# Supply.net
KiCad netlist of a schematic drawn in Altium Designer
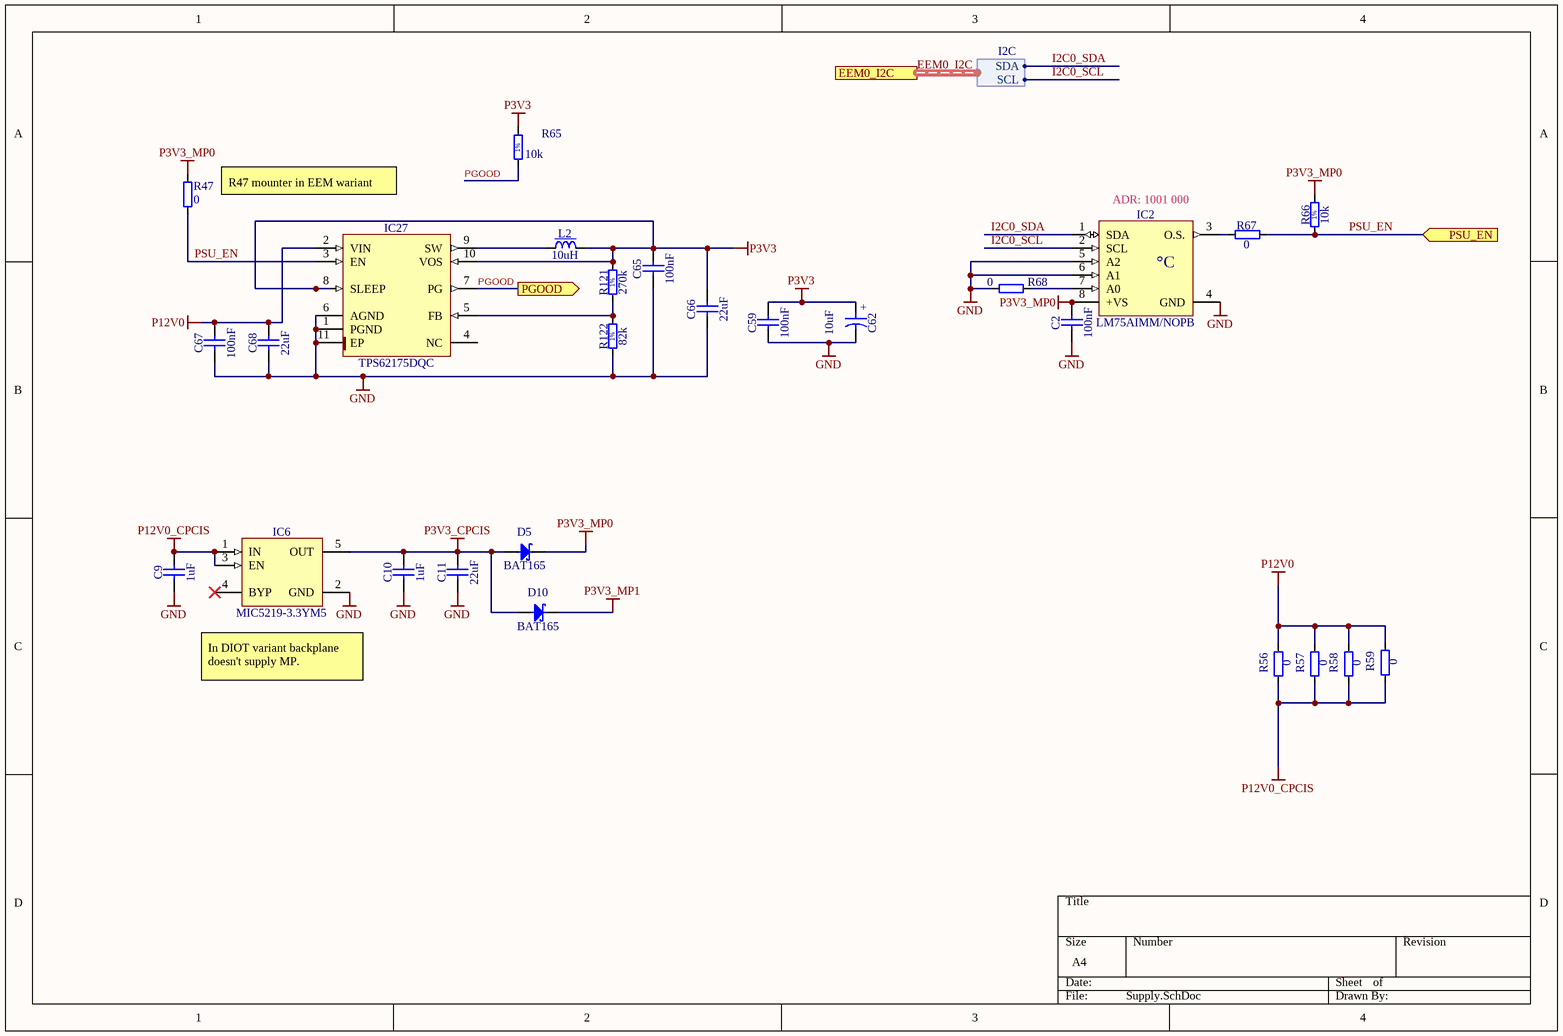
[diagram p0: Supply.SchDoc]

(export (version "E")
  (design (tool "Eeschema 10.0.6"))
  (components
    (comp (ref "C2")
      (value "100nF")
      (footprint "CAPC1005X55N")
      (description "Non-polarised capacitor")
      (fields
        (field (name "PART NUMBER") "CC0402_100NF_16V_10%_X5R")
        (field (name "VOLTAGE") "16V")
        (field (name "AUTHOR") "CERN DEM JLC")
      )
      (libsource (lib "Capacitors") (part "Capacitor - non polarized"))
    )
    (comp (ref "C9")
      (value "1uF")
      (footprint "CAPC1608X87N")
      (description "Non-polarised capacitor")
      (fields
        (field (name "PART NUMBER") "CC0603_1UF_25V_10%_X7R")
        (field (name "VOLTAGE") "25V")
        (field (name "AUTHOR") "CERN DEM JLC")
      )
      (libsource (lib "Capacitors") (part "Capacitor - non polarized"))
    )
    (comp (ref "C10")
      (value "1uF")
      (footprint "CAPC1608X87N")
      (description "Non-polarised capacitor")
      (fields
        (field (name "PART NUMBER") "CC0603_1UF_25V_10%_X7R")
        (field (name "VOLTAGE") "25V")
        (field (name "AUTHOR") "CERN DEM JLC")
      )
      (libsource (lib "Capacitors") (part "Capacitor - non polarized"))
    )
    (comp (ref "C11")
      (value "22uF")
      (footprint "CAPC1608X90N")
      (description "Non-polarised capacitor")
      (fields
        (field (name "PART NUMBER") "CC0603_22UF_6.3V_20%_X5R")
        (field (name "VOLTAGE") "6.3V")
        (field (name "AUTHOR") "CERN DEM JLC")
      )
      (libsource (lib "Capacitors") (part "Capacitor - non polarized"))
    )
    (comp (ref "C59")
      (value "100nF")
      (footprint "CAPC1005X55N")
      (description "Non-polarised capacitor")
      (fields
        (field (name "PART NUMBER") "CC0402_100NF_16V_10%_X5R")
        (field (name "VOLTAGE") "16V")
        (field (name "AUTHOR") "CERN DEM JLC")
      )
      (libsource (lib "Capacitors") (part "Capacitor - non polarized"))
    )
    (comp (ref "C62")
      (value "10uF")
      (footprint "CAPAE430X540N")
      (description "Polarised capacitor")
      (fields
        (field (name "PART NUMBER") "CAE430-540_10UF_16V_20%")
        (field (name "VOLTAGE") "16V")
        (field (name "AUTHOR") "CERN DEM JLC")
      )
      (libsource (lib "Capacitors") (part "Capacitor - polarized"))
    )
    (comp (ref "C65")
      (value "100nF")
      (footprint "CAPC1005X55N")
      (description "Non-polarised capacitor")
      (fields
        (field (name "PART NUMBER") "CC0402_100NF_16V_10%_X5R")
        (field (name "VOLTAGE") "16V")
        (field (name "AUTHOR") "CERN DEM JLC")
      )
      (libsource (lib "Capacitors") (part "Capacitor - non polarized"))
    )
    (comp (ref "C66")
      (value "22uF")
      (footprint "CAPC2012X135N")
      (description "Non-polarised capacitor")
      (fields
        (field (name "PART NUMBER") "CC0805_22UF_16V_10%_X5R")
        (field (name "VOLTAGE") "16V")
        (field (name "AUTHOR") "CERN DEM JLC")
      )
      (libsource (lib "Capacitors") (part "Capacitor - non polarized"))
    )
    (comp (ref "C67")
      (value "100nF")
      (footprint "CAPC1005X55N")
      (description "Non-polarised capacitor")
      (fields
        (field (name "PART NUMBER") "CC0402_100NF_16V_10%_X5R")
        (field (name "VOLTAGE") "16V")
        (field (name "AUTHOR") "CERN DEM JLC")
      )
      (libsource (lib "Capacitors") (part "Capacitor - non polarized"))
    )
    (comp (ref "C68")
      (value "22uF")
      (footprint "CAPC2012X135N")
      (description "Non-polarised capacitor")
      (fields
        (field (name "PART NUMBER") "CC0805_22UF_16V_10%_X5R")
        (field (name "VOLTAGE") "16V")
        (field (name "AUTHOR") "CERN DEM JLC")
      )
      (libsource (lib "Capacitors") (part "Capacitor - non polarized"))
    )
    (comp (ref "D5")
      (value "BAT165")
      (footprint "SOD2512X110N")
      (description "Schottky Diode")
      (fields
        (field (name "MANUFACTURER") "INFINEON")
        (field (name "VOLTAGE") "40V")
        (field (name "AUTHOR") "CERN DEM JLC")
      )
      (libsource (lib "ICs And Semiconductors") (part "Diode Schottky"))
    )
    (comp (ref "D10")
      (value "BAT165")
      (footprint "SOD2512X110N")
      (description "Schottky Diode")
      (fields
        (field (name "MANUFACTURER") "INFINEON")
        (field (name "VOLTAGE") "40V")
        (field (name "AUTHOR") "CERN DEM JLC")
      )
      (libsource (lib "ICs And Semiconductors") (part "Diode Schottky"))
    )
    (comp (ref "IC2")
      (value "LM75AIMM/NOPB")
      (footprint "SOP65P490X109-8N")
      (description "Digital Temperature Sensor and Thermal Watchdog with Two-Wire Interface")
      (fields (field (name "MANUFACTURER") "TEXAS INSTRUMENTS") (field (name "AUTHOR") "CERN DEM JLC"))
      (libsource (lib "ICs And Semiconductors") (part "LM75"))
    )
    (comp (ref "IC6")
      (value "MIC5219-3.3YM5")
      (footprint "SOT95P280X145-5N")
      (description "500mA Peak Output LDO Regulator")
      (fields (field (name "MANUFACTURER") "MICROCHIP TECHNOLOGY") (field (name "AUTHOR") "CERN DEM WB"))
      (libsource (lib "ICs And Semiconductors") (part "MIC5219-X.XYM5"))
    )
    (comp (ref "IC27")
      (value "TPS62175DQC")
      (footprint "SON50P200X300X80-11N-R94X250")
      (description "4.75-28VDC to 1-6VDC, 500mA Step-Down Converter With Sleep Mode")
      (fields (field (name "MANUFACTURER") "TEXAS INSTRUMENTS") (field (name "AUTHOR") "CERN DEM JMW"))
      (libsource (lib "ICs And Semiconductors") (part "TPS62175"))
    )
    (comp (ref "L2")
      (value "10uH")
      (footprint "IND_MURATA-PS_8400")
      (description "Inductor With Core")
      (fields
        (field (name "PART NUMBER") "IND_10UH_10%_MURATA-PS_8400")
        (field (name "POWER") "950mA")
        (field (name "AUTHOR") "CERN DEM JLC")
      )
      (libsource (lib "Inductors & Transformers") (part "Inductor With Magnetic core"))
    )
    (comp (ref "R47")
      (value "0")
      (footprint "RESC1005X40N")
      (description "Resistor")
      (fields
        (field (name "PART NUMBER") "R0402_0R_JUMPER")
        (field (name "MANUFACTURER") "GENERIC")
        (field (name "AUTHOR") "CERN DEM JLC")
      )
      (libsource (lib "Resistors") (part "Resistor"))
    )
    (comp (ref "R56")
      (value "0")
      (footprint "RESC1005X35N")
      (description "Resistor")
      (fields
        (field (name "PART NUMBER") "R0603_0R_JUMPER")
        (field (name "MANUFACTURER") "GENERIC")
        (field (name "AUTHOR") "CERN DEM JLC")
      )
      (libsource (lib "Resistors") (part "Resistor"))
    )
    (comp (ref "R57")
      (value "0")
      (footprint "RESC1005X35N")
      (description "Resistor")
      (fields
        (field (name "PART NUMBER") "R0603_0R_JUMPER")
        (field (name "MANUFACTURER") "GENERIC")
        (field (name "AUTHOR") "CERN DEM JLC")
      )
      (libsource (lib "Resistors") (part "Resistor"))
    )
    (comp (ref "R58")
      (value "0")
      (footprint "RESC1005X35N")
      (description "Resistor")
      (fields
        (field (name "PART NUMBER") "R0603_0R_JUMPER")
        (field (name "MANUFACTURER") "GENERIC")
        (field (name "AUTHOR") "CERN DEM JLC")
      )
      (libsource (lib "Resistors") (part "Resistor"))
    )
    (comp (ref "R59")
      (value "0")
      (footprint "RESC1005X35N")
      (description "Resistor")
      (fields
        (field (name "PART NUMBER") "R0603_0R_JUMPER")
        (field (name "MANUFACTURER") "GENERIC")
        (field (name "AUTHOR") "CERN DEM JLC")
      )
      (libsource (lib "Resistors") (part "Resistor"))
    )
    (comp (ref "R65")
      (value "10k")
      (footprint "RESC1005X40N")
      (description "Resistor - 1%")
      (fields
        (field (name "PART NUMBER") "R0402_10K_1%_0.0625W_100PPM")
        (field (name "POWER") "0.0625W")
        (field (name "AUTHOR") "CERN DEM JLC")
      )
      (libsource (lib "Resistors") (part "Resistor - 1%"))
    )
    (comp (ref "R66")
      (value "10k")
      (footprint "RESC1005X40N")
      (description "Resistor - 1%")
      (fields
        (field (name "PART NUMBER") "R0402_10K_1%_0.0625W_100PPM")
        (field (name "POWER") "0.0625W")
        (field (name "AUTHOR") "CERN DEM JLC")
      )
      (libsource (lib "Resistors") (part "Resistor - 1%"))
    )
    (comp (ref "R67")
      (value "0")
      (footprint "RESC1005X35N")
      (description "Resistor")
      (fields
        (field (name "PART NUMBER") "R0402_0R_JUMPER")
        (field (name "MANUFACTURER") "GENERIC")
        (field (name "AUTHOR") "CERN DEM JLC")
      )
      (libsource (lib "Resistors") (part "Resistor"))
    )
    (comp (ref "R68")
      (value "0")
      (footprint "RESC1005X35N")
      (description "Resistor")
      (fields
        (field (name "PART NUMBER") "R0402_0R_JUMPER")
        (field (name "MANUFACTURER") "GENERIC")
        (field (name "AUTHOR") "CERN DEM JLC")
      )
      (libsource (lib "Resistors") (part "Resistor"))
    )
    (comp (ref "R121")
      (value "270k")
      (footprint "RESC1608X55N")
      (description "Resistor - 1%")
      (fields
        (field (name "PART NUMBER") "R0603_270K_1%_0.1W_100PPM")
        (field (name "POWER") "0.1W")
        (field (name "AUTHOR") "CERN DEM JLC")
      )
      (libsource (lib "Resistors") (part "Resistor - 1%"))
    )
    (comp (ref "R122")
      (value "82k")
      (footprint "RESC1608X55N")
      (description "Resistor - 1%")
      (fields
        (field (name "PART NUMBER") "R0603_82K_1%_0.1W_100PPM")
        (field (name "POWER") "0.1W")
        (field (name "AUTHOR") "CERN DEM JLC")
      )
      (libsource (lib "Resistors") (part "Resistor - 1%"))
    )
  )
  (nets
    (net (code "3") (name "/I2C0_SCL") (class "Default")
      (node (ref "IC2") (pin "2") (pinfunction "SCL_2") (pintype "input"))
    )
    (net (code "4") (name "/I2C0_SDA") (class "Default")
      (node (ref "IC2") (pin "1") (pinfunction "SDA_1") (pintype "bidirectional"))
    )
    (net (code "5") (name "/PGOOD") (class "Default")
      (node (ref "IC27") (pin "7") (pinfunction "PG_7") (pintype "output"))
      (node (ref "R65") (pin "1") (pinfunction "1_1") (pintype "passive"))
    )
    (net (code "6") (name "/PSU_EN") (class "Default")
      (node (ref "IC27") (pin "3") (pinfunction "EN_3") (pintype "input"))
      (node (ref "R47") (pin "1") (pinfunction "1_1") (pintype "passive"))
      (node (ref "R66") (pin "1") (pinfunction "1_1") (pintype "passive"))
      (node (ref "R67") (pin "2") (pinfunction "2_2") (pintype "passive"))
    )
    (net (code "7") (name "GND") (class "Default")
      (node (ref "C10") (pin "1") (pinfunction "1_1") (pintype "passive"))
      (node (ref "C11") (pin "1") (pinfunction "1_1") (pintype "passive"))
      (node (ref "C2") (pin "1") (pinfunction "1_1") (pintype "passive"))
      (node (ref "C59") (pin "1") (pinfunction "1_1") (pintype "passive"))
      (node (ref "C62") (pin "2") (pinfunction "2_2") (pintype "passive"))
      (node (ref "C65") (pin "1") (pinfunction "1_1") (pintype "passive"))
      (node (ref "C66") (pin "1") (pinfunction "1_1") (pintype "passive"))
      (node (ref "C67") (pin "1") (pinfunction "1_1") (pintype "passive"))
      (node (ref "C68") (pin "1") (pinfunction "1_1") (pintype "passive"))
      (node (ref "C9") (pin "1") (pinfunction "1_1") (pintype "passive"))
      (node (ref "IC2") (pin "4") (pinfunction "GND_4") (pintype "power_in"))
      (node (ref "IC2") (pin "5") (pinfunction "A2_5") (pintype "input"))
      (node (ref "IC2") (pin "6") (pinfunction "A1_6") (pintype "input"))
      (node (ref "IC27") (pin "1") (pinfunction "PGND_1") (pintype "power_in"))
      (node (ref "IC27") (pin "11") (pinfunction "EP_11") (pintype "power_in"))
      (node (ref "IC27") (pin "6") (pinfunction "AGND_6") (pintype "power_in"))
      (node (ref "IC6") (pin "2") (pinfunction "GND_2") (pintype "power_in"))
      (node (ref "R122") (pin "1") (pinfunction "1_1") (pintype "passive"))
      (node (ref "R68") (pin "1") (pinfunction "1_1") (pintype "passive"))
    )
    (net (code "8") (name "Net-(IC2-A0)") (class "Default")
      (node (ref "IC2") (pin "7") (pinfunction "A0_7") (pintype "input"))
      (node (ref "R68") (pin "2") (pinfunction "2_2") (pintype "passive"))
    )
    (net (code "9") (name "Net-(IC2-O.S.)") (class "Default")
      (node (ref "IC2") (pin "3") (pinfunction "O.S._3") (pintype "output"))
      (node (ref "R67") (pin "1") (pinfunction "1_1") (pintype "passive"))
    )
    (net (code "10") (name "Net-(IC27-FB)") (class "Default")
      (node (ref "IC27") (pin "5") (pinfunction "FB_5") (pintype "input"))
      (node (ref "R121") (pin "1") (pinfunction "1_1") (pintype "passive"))
      (node (ref "R122") (pin "2") (pinfunction "2_2") (pintype "passive"))
    )
    (net (code "11") (name "Net-(IC27-SW)") (class "Default")
      (node (ref "IC27") (pin "9") (pinfunction "SW_9") (pintype "output"))
      (node (ref "L2") (pin "1") (pinfunction "1_1") (pintype "passive"))
    )
    (net (code "12") (name "P3V3") (class "Default")
      (node (ref "C59") (pin "2") (pinfunction "2_2") (pintype "passive"))
      (node (ref "C62") (pin "1") (pinfunction "1_1") (pintype "passive"))
      (node (ref "C65") (pin "2") (pinfunction "2_2") (pintype "passive"))
      (node (ref "C66") (pin "2") (pinfunction "2_2") (pintype "passive"))
      (node (ref "IC27") (pin "10") (pinfunction "VOS_10") (pintype "input"))
      (node (ref "IC27") (pin "8") (pinfunction "SLEEP_8") (pintype "input"))
      (node (ref "L2") (pin "2") (pinfunction "2_2") (pintype "passive"))
      (node (ref "R121") (pin "2") (pinfunction "2_2") (pintype "passive"))
      (node (ref "R65") (pin "2") (pinfunction "2_2") (pintype "passive"))
    )
    (net (code "13") (name "P3V3_CPCIS") (class "Default")
      (node (ref "C10") (pin "2") (pinfunction "2_2") (pintype "passive"))
      (node (ref "C11") (pin "2") (pinfunction "2_2") (pintype "passive"))
      (node (ref "D10") (pin "2") (pinfunction "A_2") (pintype "passive"))
      (node (ref "D5") (pin "2") (pinfunction "A_2") (pintype "passive"))
      (node (ref "IC6") (pin "5") (pinfunction "OUT_5") (pintype "power_in"))
    )
    (net (code "14") (name "P3V3_MP0") (class "Default")
      (node (ref "C2") (pin "2") (pinfunction "2_2") (pintype "passive"))
      (node (ref "D5") (pin "1") (pinfunction "C_1") (pintype "passive"))
      (node (ref "IC2") (pin "8") (pinfunction "+VS_8") (pintype "power_in"))
      (node (ref "R47") (pin "2") (pinfunction "2_2") (pintype "passive"))
      (node (ref "R66") (pin "2") (pinfunction "2_2") (pintype "passive"))
    )
    (net (code "15") (name "P3V3_MP1") (class "Default")
      (node (ref "D10") (pin "1") (pinfunction "C_1") (pintype "passive"))
    )
    (net (code "16") (name "P12V0") (class "Default")
      (node (ref "C67") (pin "2") (pinfunction "2_2") (pintype "passive"))
      (node (ref "C68") (pin "2") (pinfunction "2_2") (pintype "passive"))
      (node (ref "IC27") (pin "2") (pinfunction "VIN_2") (pintype "input"))
      (node (ref "R56") (pin "1") (pinfunction "1_1") (pintype "passive"))
      (node (ref "R57") (pin "1") (pinfunction "1_1") (pintype "passive"))
      (node (ref "R58") (pin "1") (pinfunction "1_1") (pintype "passive"))
      (node (ref "R59") (pin "1") (pinfunction "1_1") (pintype "passive"))
    )
    (net (code "17") (name "P12V0_CPCIS") (class "Default")
      (node (ref "C9") (pin "2") (pinfunction "2_2") (pintype "passive"))
      (node (ref "IC6") (pin "1") (pinfunction "IN_1") (pintype "input"))
      (node (ref "IC6") (pin "3") (pinfunction "EN_3") (pintype "input"))
      (node (ref "R56") (pin "2") (pinfunction "2_2") (pintype "passive"))
      (node (ref "R57") (pin "2") (pinfunction "2_2") (pintype "passive"))
      (node (ref "R58") (pin "2") (pinfunction "2_2") (pintype "passive"))
      (node (ref "R59") (pin "2") (pinfunction "2_2") (pintype "passive"))
    )
    (net (code "18") (name "unconnected-(IC6-BYP-Pad4)") (class "Default")
      (node (ref "IC6") (pin "4") (pinfunction "BYP_4") (pintype "passive+no_connect"))
    )
    (net (code "19") (name "unconnected-(IC27-NC-Pad4)") (class "Default")
      (node (ref "IC27") (pin "4") (pinfunction "NC_4") (pintype "passive"))
    )
  )
)
